# MicDSP.net
KiCad netlist of a schematic drawn in Altium Designer
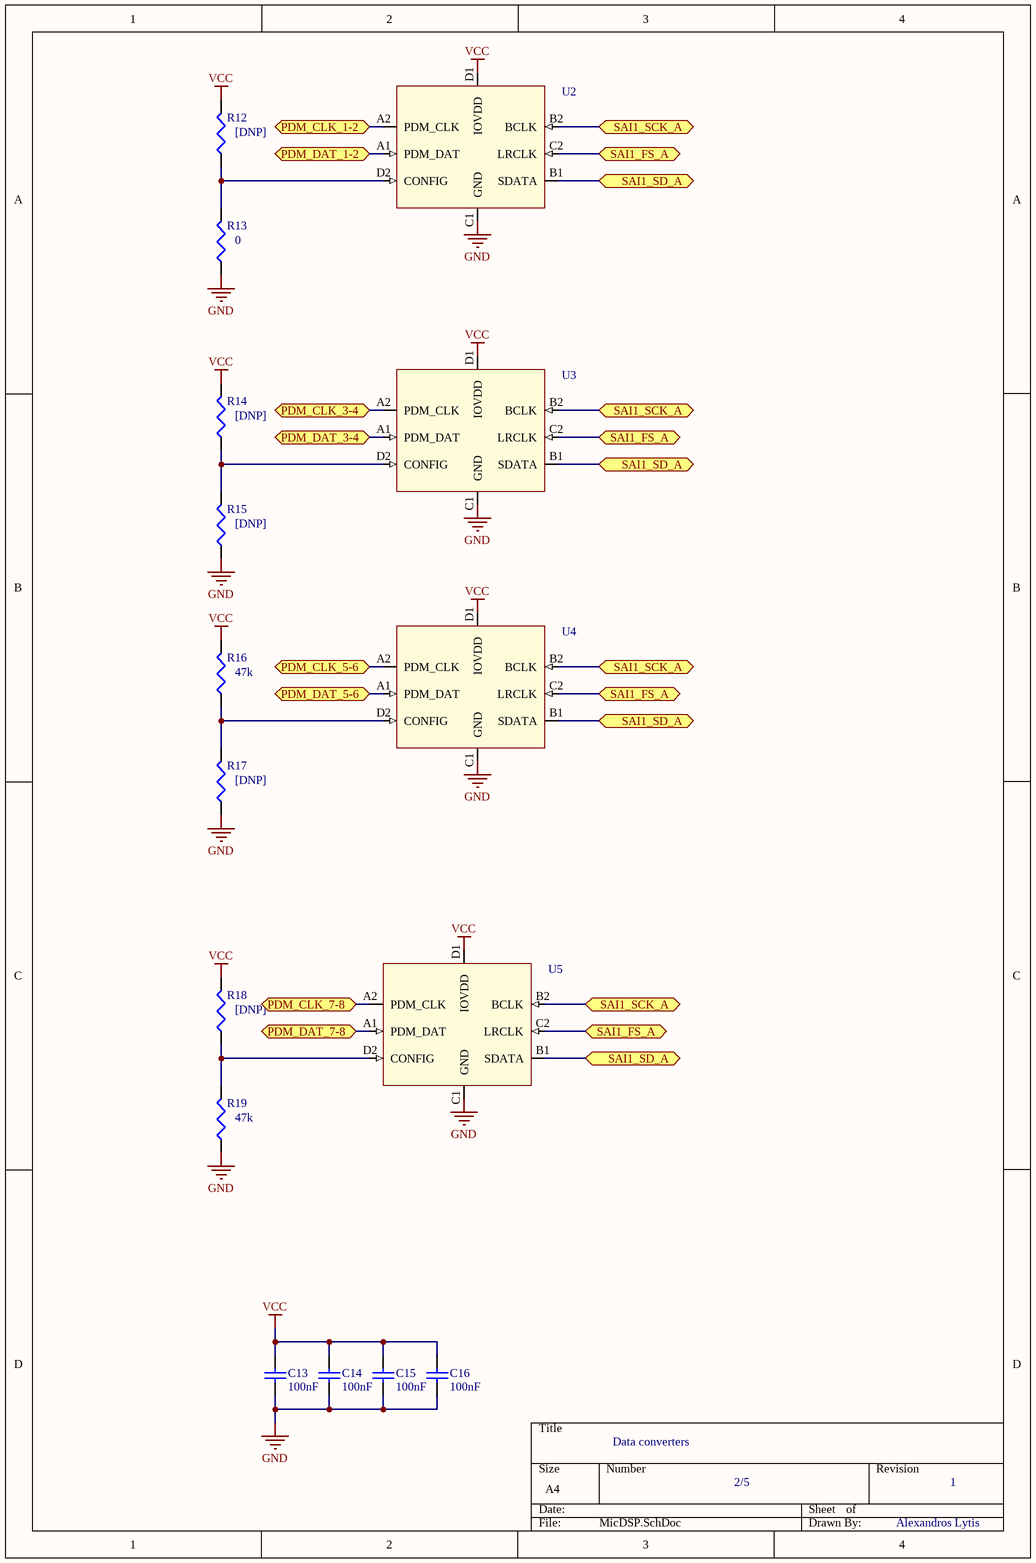
[diagram p0: MicDSP.SchDoc]

(export (version "E")
  (design (tool "Eeschema 10.0.6"))
  (components
    (comp (ref "C13")
      (value "100nF")
      (footprint "CAP0603")
      (description "Capacitor (Semiconductor SIM Model)")
      (fields (field (name "Comment") "Cap Semi") (field (name "PUBLISHER") "Altium Limited"))
      (libsource (lib "Miscellaneous Devices") (part "Cap Semi"))
    )
    (comp (ref "C14")
      (value "100nF")
      (footprint "CAP0603")
      (description "Capacitor (Semiconductor SIM Model)")
      (fields (field (name "Comment") "Cap Semi") (field (name "PUBLISHER") "Altium Limited"))
      (libsource (lib "Miscellaneous Devices") (part "Cap Semi"))
    )
    (comp (ref "C15")
      (value "100nF")
      (footprint "CAP0603")
      (description "Capacitor (Semiconductor SIM Model)")
      (fields (field (name "Comment") "Cap Semi") (field (name "PUBLISHER") "Altium Limited"))
      (libsource (lib "Miscellaneous Devices") (part "Cap Semi"))
    )
    (comp (ref "C16")
      (value "100nF")
      (footprint "CAP0603")
      (description "Capacitor (Semiconductor SIM Model)")
      (fields (field (name "Comment") "Cap Semi") (field (name "PUBLISHER") "Altium Limited"))
      (libsource (lib "Miscellaneous Devices") (part "Cap Semi"))
    )
    (comp (ref "R12")
      (value "[DNP]")
      (footprint "RES0603")
      (description "Resistor")
      (fields (field (name "Comment") "Res3") (field (name "PUBLISHER") "Altium Limited"))
      (libsource (lib "Miscellaneous Devices") (part "Res3"))
    )
    (comp (ref "R13")
      (value "0")
      (footprint "RES0603")
      (description "Resistor")
      (fields (field (name "Comment") "Res3") (field (name "PUBLISHER") "Altium Limited"))
      (libsource (lib "Miscellaneous Devices") (part "Res3"))
    )
    (comp (ref "R14")
      (value "[DNP]")
      (footprint "RES0603")
      (description "Resistor")
      (fields (field (name "Comment") "Res3") (field (name "PUBLISHER") "Altium Limited"))
      (libsource (lib "Miscellaneous Devices") (part "Res3"))
    )
    (comp (ref "R15")
      (value "[DNP]")
      (footprint "RES0603")
      (description "Resistor")
      (fields (field (name "Comment") "Res3") (field (name "PUBLISHER") "Altium Limited"))
      (libsource (lib "Miscellaneous Devices") (part "Res3"))
    )
    (comp (ref "R16")
      (value "47k")
      (footprint "RES0603")
      (description "Resistor")
      (fields (field (name "Comment") "Res3") (field (name "PUBLISHER") "Altium Limited"))
      (libsource (lib "Miscellaneous Devices") (part "Res3"))
    )
    (comp (ref "R17")
      (value "[DNP]")
      (footprint "RES0603")
      (description "Resistor")
      (fields (field (name "Comment") "Res3") (field (name "PUBLISHER") "Altium Limited"))
      (libsource (lib "Miscellaneous Devices") (part "Res3"))
    )
    (comp (ref "R18")
      (value "[DNP]")
      (footprint "RES0603")
      (description "Resistor")
      (fields (field (name "Comment") "Res3") (field (name "PUBLISHER") "Altium Limited"))
      (libsource (lib "Miscellaneous Devices") (part "Res3"))
    )
    (comp (ref "R19")
      (value "47k")
      (footprint "RES0603")
      (description "Resistor")
      (fields (field (name "Comment") "Res3") (field (name "PUBLISHER") "Altium Limited"))
      (libsource (lib "Miscellaneous Devices") (part "Res3"))
    )
    (comp (ref "U2")
      (value "ADAU7002")
      (footprint "ADAU7002_")
      (libsource (lib "Custom_Libraries") (part "ADAU7002"))
    )
    (comp (ref "U3")
      (value "ADAU7002")
      (footprint "ADAU7002_")
      (libsource (lib "Custom_Libraries") (part "ADAU7002"))
    )
    (comp (ref "U4")
      (value "ADAU7002")
      (footprint "ADAU7002_")
      (libsource (lib "Custom_Libraries") (part "ADAU7002"))
    )
    (comp (ref "U5")
      (value "ADAU7002")
      (footprint "ADAU7002_")
      (libsource (lib "Custom_Libraries") (part "ADAU7002"))
    )
  )
  (nets
    (net (code "1") (name "/PDM_CLK_1-2") (class "Default")
      (node (ref "U2") (pin "A2") (pinfunction "PDM_CLK_A2") (pintype "bidirectional"))
    )
    (net (code "2") (name "/PDM_CLK_3-4") (class "Default")
      (node (ref "U3") (pin "A2") (pinfunction "PDM_CLK_A2") (pintype "bidirectional"))
    )
    (net (code "3") (name "/PDM_CLK_5-6") (class "Default")
      (node (ref "U4") (pin "A2") (pinfunction "PDM_CLK_A2") (pintype "bidirectional"))
    )
    (net (code "4") (name "/PDM_CLK_7-8") (class "Default")
      (node (ref "U5") (pin "A2") (pinfunction "PDM_CLK_A2") (pintype "bidirectional"))
    )
    (net (code "5") (name "/PDM_DAT_1-2") (class "Default")
      (node (ref "U2") (pin "A1") (pinfunction "PDM_DAT_A1") (pintype "input"))
    )
    (net (code "6") (name "/PDM_DAT_3-4") (class "Default")
      (node (ref "U3") (pin "A1") (pinfunction "PDM_DAT_A1") (pintype "input"))
    )
    (net (code "7") (name "/PDM_DAT_5-6") (class "Default")
      (node (ref "U4") (pin "A1") (pinfunction "PDM_DAT_A1") (pintype "input"))
    )
    (net (code "8") (name "/PDM_DAT_7-8") (class "Default")
      (node (ref "U5") (pin "A1") (pinfunction "PDM_DAT_A1") (pintype "input"))
    )
    (net (code "9") (name "/SAI1_FS_A") (class "Default")
      (node (ref "U2") (pin "C2") (pinfunction "LRCLK_C2") (pintype "input"))
      (node (ref "U3") (pin "C2") (pinfunction "LRCLK_C2") (pintype "input"))
      (node (ref "U4") (pin "C2") (pinfunction "LRCLK_C2") (pintype "input"))
      (node (ref "U5") (pin "C2") (pinfunction "LRCLK_C2") (pintype "input"))
    )
    (net (code "10") (name "/SAI1_SCK_A") (class "Default")
      (node (ref "U2") (pin "B2") (pinfunction "BCLK_B2") (pintype "input"))
      (node (ref "U3") (pin "B2") (pinfunction "BCLK_B2") (pintype "input"))
      (node (ref "U4") (pin "B2") (pinfunction "BCLK_B2") (pintype "input"))
      (node (ref "U5") (pin "B2") (pinfunction "BCLK_B2") (pintype "input"))
    )
    (net (code "11") (name "/SAI1_SD_A") (class "Default")
      (node (ref "U2") (pin "B1") (pinfunction "SDATA_B1") (pintype "bidirectional"))
      (node (ref "U3") (pin "B1") (pinfunction "SDATA_B1") (pintype "bidirectional"))
      (node (ref "U4") (pin "B1") (pinfunction "SDATA_B1") (pintype "bidirectional"))
      (node (ref "U5") (pin "B1") (pinfunction "SDATA_B1") (pintype "bidirectional"))
    )
    (net (code "12") (name "GND") (class "Default")
      (node (ref "C13") (pin "1") (pinfunction "1_1") (pintype "passive"))
      (node (ref "C14") (pin "1") (pinfunction "1_1") (pintype "passive"))
      (node (ref "C15") (pin "1") (pinfunction "1_1") (pintype "passive"))
      (node (ref "C16") (pin "1") (pinfunction "1_1") (pintype "passive"))
      (node (ref "R13") (pin "1") (pinfunction "1_1") (pintype "passive"))
      (node (ref "R15") (pin "1") (pinfunction "1_1") (pintype "passive"))
      (node (ref "R17") (pin "1") (pinfunction "1_1") (pintype "passive"))
      (node (ref "R19") (pin "1") (pinfunction "1_1") (pintype "passive"))
      (node (ref "U2") (pin "C1") (pinfunction "GND_C1") (pintype "power_in"))
      (node (ref "U3") (pin "C1") (pinfunction "GND_C1") (pintype "power_in"))
      (node (ref "U4") (pin "C1") (pinfunction "GND_C1") (pintype "power_in"))
      (node (ref "U5") (pin "C1") (pinfunction "GND_C1") (pintype "power_in"))
    )
    (net (code "13") (name "Net-(U2-CONFIG)") (class "Default")
      (node (ref "R12") (pin "1") (pinfunction "1_1") (pintype "passive"))
      (node (ref "R13") (pin "2") (pinfunction "2_2") (pintype "passive"))
      (node (ref "U2") (pin "D2") (pinfunction "CONFIG_D2") (pintype "input"))
    )
    (net (code "14") (name "Net-(U3-CONFIG)") (class "Default")
      (node (ref "R14") (pin "1") (pinfunction "1_1") (pintype "passive"))
      (node (ref "R15") (pin "2") (pinfunction "2_2") (pintype "passive"))
      (node (ref "U3") (pin "D2") (pinfunction "CONFIG_D2") (pintype "input"))
    )
    (net (code "15") (name "Net-(U4-CONFIG)") (class "Default")
      (node (ref "R16") (pin "1") (pinfunction "1_1") (pintype "passive"))
      (node (ref "R17") (pin "2") (pinfunction "2_2") (pintype "passive"))
      (node (ref "U4") (pin "D2") (pinfunction "CONFIG_D2") (pintype "input"))
    )
    (net (code "16") (name "Net-(U5-CONFIG)") (class "Default")
      (node (ref "R18") (pin "1") (pinfunction "1_1") (pintype "passive"))
      (node (ref "R19") (pin "2") (pinfunction "2_2") (pintype "passive"))
      (node (ref "U5") (pin "D2") (pinfunction "CONFIG_D2") (pintype "input"))
    )
    (net (code "17") (name "VCC") (class "Default")
      (node (ref "C13") (pin "2") (pinfunction "2_2") (pintype "passive"))
      (node (ref "C14") (pin "2") (pinfunction "2_2") (pintype "passive"))
      (node (ref "C15") (pin "2") (pinfunction "2_2") (pintype "passive"))
      (node (ref "C16") (pin "2") (pinfunction "2_2") (pintype "passive"))
      (node (ref "R12") (pin "2") (pinfunction "2_2") (pintype "passive"))
      (node (ref "R14") (pin "2") (pinfunction "2_2") (pintype "passive"))
      (node (ref "R16") (pin "2") (pinfunction "2_2") (pintype "passive"))
      (node (ref "R18") (pin "2") (pinfunction "2_2") (pintype "passive"))
      (node (ref "U2") (pin "D1") (pinfunction "IOVDD_D1") (pintype "power_in"))
      (node (ref "U3") (pin "D1") (pinfunction "IOVDD_D1") (pintype "power_in"))
      (node (ref "U4") (pin "D1") (pinfunction "IOVDD_D1") (pintype "power_in"))
      (node (ref "U5") (pin "D1") (pinfunction "IOVDD_D1") (pintype "power_in"))
    )
  )
)
